# power-v5.net
KiCad netlist of a schematic drawn in Altium Designer
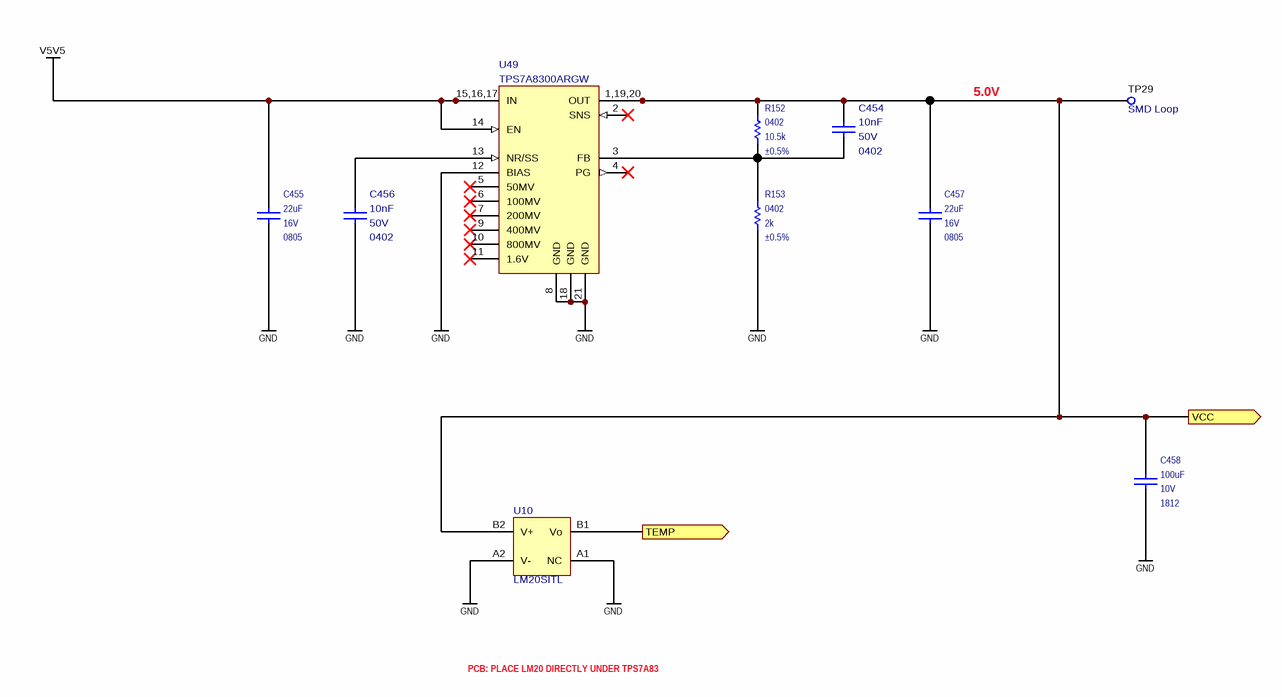
[diagram p0: power-v5.SchDoc]

(export (version "E")
  (design (tool "Eeschema 10.0.6"))
  (components
    (comp (ref "C454")
      (value "10nF")
      (footprint "generic:CAPC100X50X55L25N")
      (description "Ceramic Capacitor 10nF ±10% 50V X7R 0402")
      (fields
        (field (name "MANUFACTURER") "Murata")
        (field (name "TOLERANCE") "±10%")
        (field (name "PACKAGE") "0402")
        (field (name "VOLTAGE") "50V")
      )
      (libsource (lib "capacitors") (part "CAP"))
    )
    (comp (ref "C455")
      (value "22uF")
      (footprint "generic:CAPC200X125X145L45N")
      (description "Ceramic Capacitor 22uF ±10% 16V X5R 0805")
      (fields
        (field (name "MANUFACTURER") "Samsung")
        (field (name "VOLTAGE") "16V")
        (field (name "PACKAGE") "0805")
        (field (name "TOLERANCE") "±10%")
      )
      (libsource (lib "generic") (part "CAP 0603"))
    )
    (comp (ref "C456")
      (value "10nF")
      (footprint "generic:CAPC100X50X55L25N")
      (description "Ceramic Capacitor 10nF ±10% 50V X7R 0402")
      (fields
        (field (name "MANUFACTURER") "Murata")
        (field (name "TOLERANCE") "±10%")
        (field (name "PACKAGE") "0402")
        (field (name "VOLTAGE") "50V")
      )
      (libsource (lib "capacitors") (part "CAP"))
    )
    (comp (ref "C457")
      (value "22uF")
      (footprint "generic:CAPC200X125X145L45N")
      (description "Ceramic Capacitor 22uF ±10% 16V X5R 0805")
      (fields
        (field (name "MANUFACTURER") "Samsung")
        (field (name "VOLTAGE") "16V")
        (field (name "PACKAGE") "0805")
        (field (name "TOLERANCE") "±10%")
      )
      (libsource (lib "generic") (part "CAP 0603"))
    )
    (comp (ref "C458")
      (value "100uF")
      (footprint "generic:CAPC450X320X360L20N")
      (description "Ceramic Capacitor 100uF ±20% 10V X5R 1812")
      (fields
        (field (name "MANUFACTURER") "TDK")
        (field (name "VOLTAGE") "10V")
        (field (name "PACKAGE") "1812")
        (field (name "TOLERANCE") "±20%")
      )
      (libsource (lib "generic") (part "CAP 0603"))
    )
    (comp (ref "R152")
      (value "10.5k")
      (footprint "RESC1005X40N")
      (description "Thin Film Resistor 10.5k +/-0.5% SMD 0402")
      (fields
        (field (name "TOLERANCE") "±0.5%")
        (field (name "MANUFACTURER") "Yageo")
        (field (name "POWER") "0.063W")
        (field (name "PACKAGE") "0402")
      )
      (libsource (lib "generic") (part "RES"))
    )
    (comp (ref "R153")
      (value "2k")
      (footprint "RESC1005X40N")
      (description "Thin Film Resistor 2k +/-0.5% SMD 0402")
      (fields
        (field (name "TOLERANCE") "±0.5%")
        (field (name "MANUFACTURER") "Susumu")
        (field (name "PACKAGE") "0402")
        (field (name "Comment") "RR0510P-202-D")
      )
      (libsource (lib "generic") (part "RES"))
    )
    (comp (ref "TP29")
      (value "5015")
      (footprint "keystone:5015")
      (description "Test Point SMD")
      (fields (field (name "MANUFACTURER") "Keystone") (field (name "NOTES") "SMD Loop"))
      (libsource (lib "generic") (part "TEST_POINT_SMD_50"))
    )
    (comp (ref "U10")
      (value "LM20SITL")
      (footprint "YZR-4")
      (description "Analog Temperature Sensor")
      (fields (field (name "MANUFACTURER") "Texas Instruments"))
      (libsource (lib "ti") (part "LM20SITL"))
    )
    (comp (ref "U49")
      (value "TPS7A8300ARGW")
      (footprint "texas_instruments:QFN65P500X500X100-21N")
      (description "LDO Regulator, 2A, VQFN-20")
      (fields (field (name "MANUFACTURER") "Texas Instruments"))
      (libsource (lib "ti") (part "TPS7A8300ARGW"))
    )
  )
  (nets
    (net (code "1") (name "/TEMP") (class "Default")
      (node (ref "U10") (pin "B1") (pinfunction "Vo_B1") (pintype "passive"))
    )
    (net (code "2") (name "/VCC") (class "Default")
      (node (ref "C454") (pin "1") (pinfunction "1_1") (pintype "passive"))
      (node (ref "C457") (pin "2") (pinfunction "2_2") (pintype "passive"))
      (node (ref "C458") (pin "2") (pinfunction "2_2") (pintype "passive"))
      (node (ref "R152") (pin "2") (pinfunction "2_2") (pintype "passive"))
      (node (ref "TP29") (pin "1") (pinfunction "1_1") (pintype "passive"))
      (node (ref "U10") (pin "B2") (pinfunction "V+_B2") (pintype "passive"))
      (node (ref "U49") (pin "1") (pinfunction "OUT_1") (pintype "passive"))
      (node (ref "U49") (pin "19") (pinfunction "OUT_19") (pintype "passive"))
      (node (ref "U49") (pin "20") (pinfunction "OUT_20") (pintype "passive"))
    )
    (net (code "3") (name "GND") (class "Default")
      (node (ref "C455") (pin "1") (pinfunction "1_1") (pintype "passive"))
      (node (ref "C456") (pin "2") (pinfunction "2_2") (pintype "passive"))
      (node (ref "C457") (pin "1") (pinfunction "1_1") (pintype "passive"))
      (node (ref "C458") (pin "1") (pinfunction "1_1") (pintype "passive"))
      (node (ref "R153") (pin "1") (pinfunction "1_1") (pintype "passive"))
      (node (ref "U10") (pin "A1") (pinfunction "NC_A1") (pintype "passive"))
      (node (ref "U10") (pin "A2") (pinfunction "V-_A2") (pintype "passive"))
      (node (ref "U49") (pin "12") (pinfunction "BIAS_12") (pintype "power_in"))
      (node (ref "U49") (pin "18") (pinfunction "GND_18") (pintype "passive"))
      (node (ref "U49") (pin "21") (pinfunction "GND_21") (pintype "passive"))
      (node (ref "U49") (pin "8") (pinfunction "GND_8") (pintype "passive"))
    )
    (net (code "4") (name "Net-(U49-FB)") (class "Default")
      (node (ref "C454") (pin "2") (pinfunction "2_2") (pintype "passive"))
      (node (ref "R152") (pin "1") (pinfunction "1_1") (pintype "passive"))
      (node (ref "R153") (pin "2") (pinfunction "2_2") (pintype "passive"))
      (node (ref "U49") (pin "3") (pinfunction "FB_3") (pintype "passive"))
    )
    (net (code "5") (name "Net-(U49-NR{slash}SS)") (class "Default")
      (node (ref "C456") (pin "1") (pinfunction "1_1") (pintype "passive"))
      (node (ref "U49") (pin "13") (pinfunction "NR/SS_13") (pintype "input"))
    )
    (net (code "6") (name "V5V5") (class "Default")
      (node (ref "C455") (pin "2") (pinfunction "2_2") (pintype "passive"))
      (node (ref "U49") (pin "14") (pinfunction "EN_14") (pintype "input"))
      (node (ref "U49") (pin "15") (pinfunction "IN_15") (pintype "passive"))
      (node (ref "U49") (pin "16") (pinfunction "IN_16") (pintype "passive"))
      (node (ref "U49") (pin "17") (pinfunction "IN_17") (pintype "passive"))
    )
    (net (code "7") (name "unconnected-(U49-1.6V-Pad11)") (class "Default")
      (node (ref "U49") (pin "11") (pinfunction "1.6V_11") (pintype "passive+no_connect"))
    )
    (net (code "8") (name "unconnected-(U49-50MV-Pad5)") (class "Default")
      (node (ref "U49") (pin "5") (pinfunction "50MV_5") (pintype "passive+no_connect"))
    )
    (net (code "9") (name "unconnected-(U49-100MV-Pad6)") (class "Default")
      (node (ref "U49") (pin "6") (pinfunction "100MV_6") (pintype "passive+no_connect"))
    )
    (net (code "10") (name "unconnected-(U49-200MV-Pad7)") (class "Default")
      (node (ref "U49") (pin "7") (pinfunction "200MV_7") (pintype "passive+no_connect"))
    )
    (net (code "11") (name "unconnected-(U49-400MV-Pad9)") (class "Default")
      (node (ref "U49") (pin "9") (pinfunction "400MV_9") (pintype "passive+no_connect"))
    )
    (net (code "12") (name "unconnected-(U49-800MV-Pad10)") (class "Default")
      (node (ref "U49") (pin "10") (pinfunction "800MV_10") (pintype "passive+no_connect"))
    )
    (net (code "13") (name "unconnected-(U49-PG-Pad4)") (class "Default")
      (node (ref "U49") (pin "4") (pinfunction "PG_4") (pintype "output+no_connect"))
    )
    (net (code "14") (name "unconnected-(U49-SNS-Pad2)") (class "Default")
      (node (ref "U49") (pin "2") (pinfunction "SNS_2") (pintype "input+no_connect"))
    )
  )
)
